# NG2092_LEFT_OV9282.net
KiCad netlist of a schematic drawn in Altium Designer
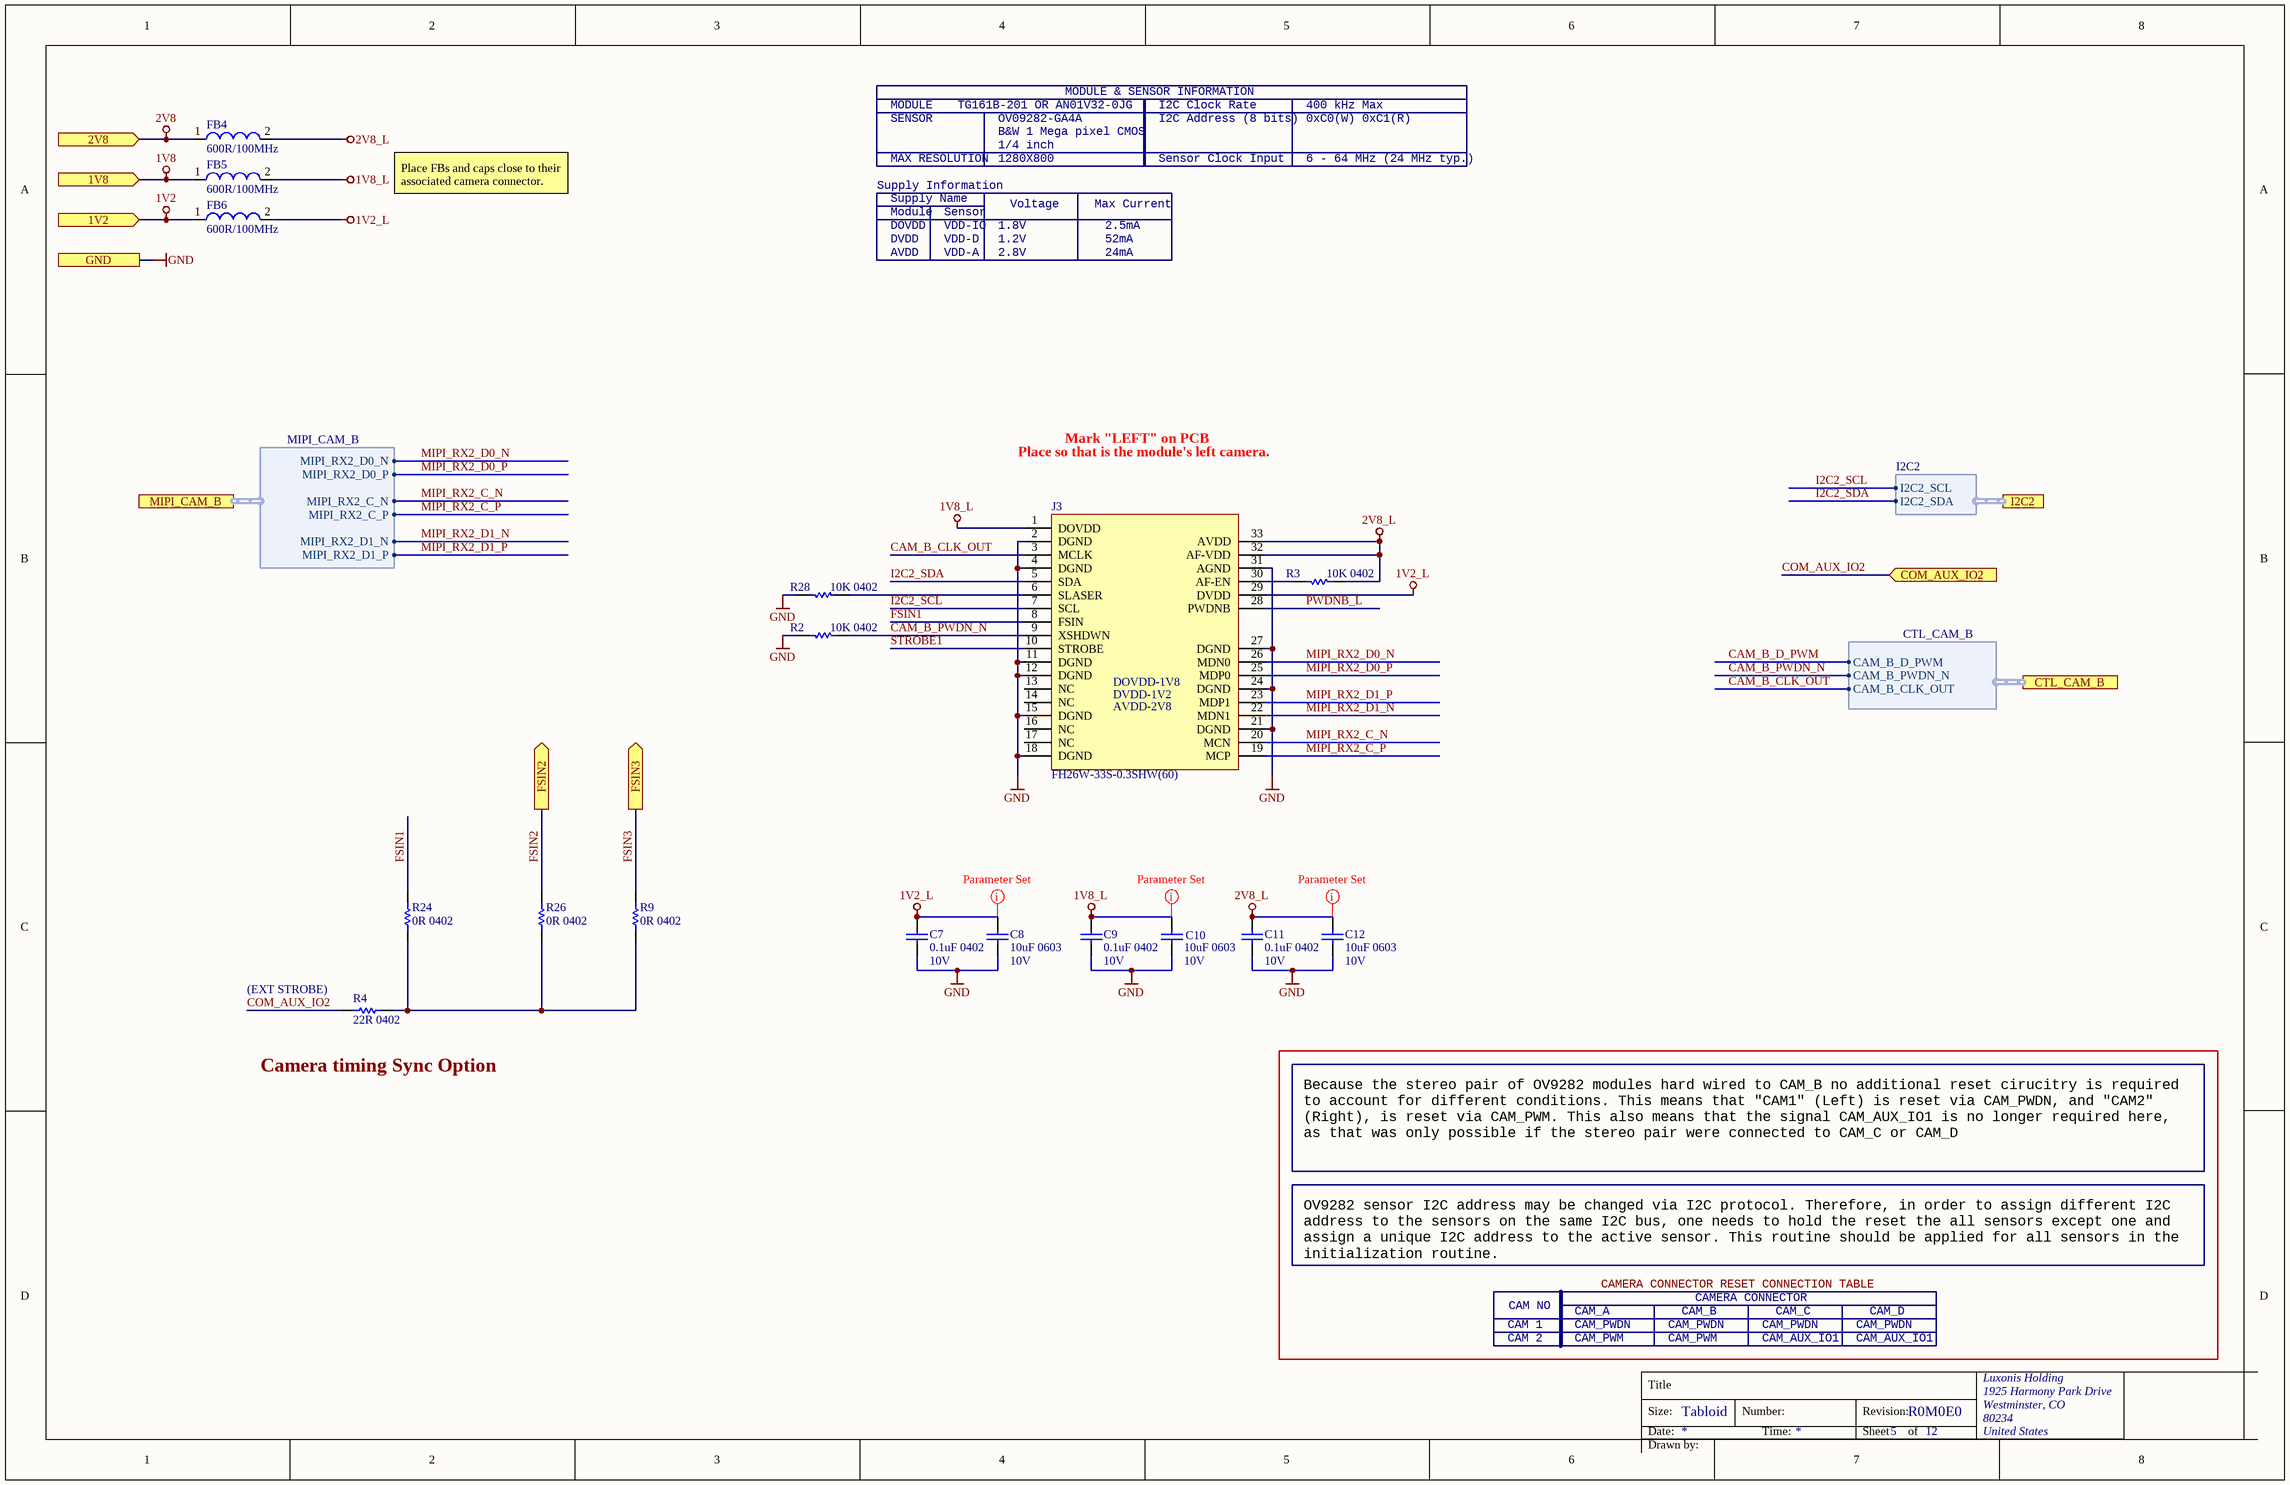
[diagram p0: NG2092_LEFT_OV9282.SchDoc]

(export (version "E")
  (design (tool "Eeschema 10.0.6"))
  (components
    (comp (ref "C7")
      (value "0.1uF 0402")
      (footprint "CAP_Altium_Vault_Generic:CAPC0402(1005)70_L")
      (description "CAP CER 0.1UF 10V X7R 0402 5%")
      (fields (field (name "TOLERANCE") "5%") (field (name "VOLTAGE RATING") "10V"))
      (libsource (lib "LuxonisMaster") (part "GRM155R71A104JA01D"))
    )
    (comp (ref "C8")
      (value "10uF 0603")
      (footprint "CAP_Altium_Vault_Generic:CAPC0603(1608)100_L")
      (description "CAP CER 10UF 10V X5R 0603 20%")
      (fields (field (name "TOLERANCE") "20%") (field (name "VOLTAGE RATING") "10V"))
      (libsource (lib "LuxonisMaster") (part "GRM188R61A106ME69D"))
    )
    (comp (ref "C9")
      (value "0.1uF 0402")
      (footprint "CAP_Altium_Vault_Generic:CAPC0402(1005)70_L")
      (description "CAP CER 0.1UF 10V X7R 0402 5%")
      (fields (field (name "TOLERANCE") "5%") (field (name "VOLTAGE RATING") "10V"))
      (libsource (lib "LuxonisMaster") (part "GRM155R71A104JA01D"))
    )
    (comp (ref "C10")
      (value "10uF 0603")
      (footprint "CAP_Altium_Vault_Generic:CAPC0603(1608)100_L")
      (description "CAP CER 10UF 10V X5R 0603 20%")
      (fields (field (name "TOLERANCE") "20%") (field (name "VOLTAGE RATING") "10V"))
      (libsource (lib "LuxonisMaster") (part "GRM188R61A106ME69D"))
    )
    (comp (ref "C11")
      (value "0.1uF 0402")
      (footprint "CAP_Altium_Vault_Generic:CAPC0402(1005)70_L")
      (description "CAP CER 0.1UF 10V X7R 0402 5%")
      (fields (field (name "TOLERANCE") "5%") (field (name "VOLTAGE RATING") "10V"))
      (libsource (lib "LuxonisMaster") (part "GRM155R71A104JA01D"))
    )
    (comp (ref "C12")
      (value "10uF 0603")
      (footprint "CAP_Altium_Vault_Generic:CAPC0603(1608)100_L")
      (description "CAP CER 10UF 10V X5R 0603 20%")
      (fields (field (name "TOLERANCE") "20%") (field (name "VOLTAGE RATING") "10V"))
      (libsource (lib "LuxonisMaster") (part "GRM188R61A106ME69D"))
    )
    (comp (ref "FB4")
      (value "600R/100MHz")
      (footprint "LuxonisMaster:2508056017Y2")
      (description "FERRITE BEAD, 0.1OHM, 2A, 0805, 600R/100MHz")
      (fields (field (name "TOLERANCE") "25%"))
      (libsource (lib "LuxonisMaster") (part "2508056017Y2"))
    )
    (comp (ref "FB5")
      (value "600R/100MHz")
      (footprint "LuxonisMaster:2508056017Y2")
      (description "FERRITE BEAD, 0.1OHM, 2A, 0805, 600R/100MHz")
      (fields (field (name "TOLERANCE") "25%"))
      (libsource (lib "LuxonisMaster") (part "2508056017Y2"))
    )
    (comp (ref "FB6")
      (value "600R/100MHz")
      (footprint "LuxonisMaster:2508056017Y2")
      (description "FERRITE BEAD, 0.1OHM, 2A, 0805, 600R/100MHz")
      (fields (field (name "TOLERANCE") "25%"))
      (libsource (lib "LuxonisMaster") (part "2508056017Y2"))
    )
    (comp (ref "J3")
      (value "FH26W-33S-0.3SHW(60)")
      (footprint "AC-PY003-OV9282")
      (description "FFC/FPC Connector, 33 Contact(s), 1 Row(s), Female, Right Angle, Surface Mount Terminal")
      (libsource (lib "NG2092") (part "AC_PY003-OV9282_CON"))
    )
    (comp (ref "R2")
      (value "10K 0402")
      (footprint "RES_Altium_Vault_Generic:RESC0402(1005)_L")
      (fields (field (name "TOLERANCE") "1%"))
      (libsource (lib "LuxonisMaster") (part "RC0402FR-1310KL"))
    )
    (comp (ref "R3")
      (value "10K 0402")
      (footprint "RES_Altium_Vault_Generic:RESC0402(1005)_L")
      (fields (field (name "TOLERANCE") "1%"))
      (libsource (lib "LuxonisMaster") (part "RC0402FR-1310KL"))
    )
    (comp (ref "R4")
      (value "22R 0402")
      (footprint "RES_Altium_Vault_Generic:RESC0402(1005)_L")
      (fields (field (name "TOLERANCE") "1%"))
      (libsource (lib "LuxonisMaster") (part "RC0402FR-1310KL"))
    )
    (comp (ref "R9")
      (value "0R 0402")
      (footprint "RES_Altium_Vault_Generic:RESC0402(1005)_L")
      (description "RES SMD 0 OHM JUMPER 1/16W 0402")
      (fields (field (name "TOLERANCE") "5%"))
      (libsource (lib "LuxonisMaster") (part "CRCW04020000Z0ED"))
    )
    (comp (ref "R24")
      (value "0R 0402")
      (footprint "RES_Altium_Vault_Generic:RESC0402(1005)_L")
      (description "RES SMD 0 OHM JUMPER 1/16W 0402")
      (fields (field (name "TOLERANCE") "5%"))
      (libsource (lib "LuxonisMaster") (part "CRCW04020000Z0ED"))
    )
    (comp (ref "R26")
      (value "0R 0402")
      (footprint "RES_Altium_Vault_Generic:RESC0402(1005)_L")
      (description "RES SMD 0 OHM JUMPER 1/16W 0402")
      (fields (field (name "TOLERANCE") "5%"))
      (libsource (lib "LuxonisMaster") (part "CRCW04020000Z0ED"))
    )
    (comp (ref "R28")
      (value "10K 0402")
      (footprint "RES_Altium_Vault_Generic:RESC0402(1005)_L")
      (fields (field (name "TOLERANCE") "1%"))
      (libsource (lib "LuxonisMaster") (part "RC0402FR-1310KL"))
    )
  )
  (nets
    (net (code "4") (name "/CAM_B_CLK_OUT") (class "Default")
      (node (ref "J3") (pin "3") (pinfunction "MCLK_3") (pintype "passive"))
    )
    (net (code "6") (name "/CAM_B_PWDN_N") (class "Default")
      (node (ref "J3") (pin "9") (pinfunction "XSHDWN_9") (pintype "passive"))
      (node (ref "R2") (pin "1") (pinfunction "1_1") (pintype "passive"))
    )
    (net (code "7") (name "/COM_AUX_IO2") (class "Default")
      (node (ref "R4") (pin "1") (pinfunction "1_1") (pintype "passive"))
    )
    (net (code "8") (name "/FSIN1") (class "Default")
      (node (ref "J3") (pin "8") (pinfunction "FSIN_8") (pintype "passive"))
      (node (ref "R24") (pin "2") (pinfunction "2_2") (pintype "passive"))
    )
    (net (code "9") (name "/FSIN2") (class "Default")
      (node (ref "R26") (pin "2") (pinfunction "2_2") (pintype "passive"))
    )
    (net (code "10") (name "/FSIN3") (class "Default")
      (node (ref "R9") (pin "1") (pinfunction "1_1") (pintype "passive"))
    )
    (net (code "11") (name "/I2C2_SCL") (class "Default")
      (node (ref "J3") (pin "7") (pinfunction "SCL_7") (pintype "passive"))
    )
    (net (code "12") (name "/I2C2_SDA") (class "Default")
      (node (ref "J3") (pin "5") (pinfunction "SDA_5") (pintype "passive"))
    )
    (net (code "13") (name "/MIPI_RX2_C_N") (class "Default")
      (node (ref "J3") (pin "20") (pinfunction "MCN_20") (pintype "passive"))
    )
    (net (code "14") (name "/MIPI_RX2_C_P") (class "Default")
      (node (ref "J3") (pin "19") (pinfunction "MCP_19") (pintype "passive"))
    )
    (net (code "15") (name "/MIPI_RX2_D0_N") (class "Default")
      (node (ref "J3") (pin "26") (pinfunction "MDN0_26") (pintype "passive"))
    )
    (net (code "16") (name "/MIPI_RX2_D0_P") (class "Default")
      (node (ref "J3") (pin "25") (pinfunction "MDP0_25") (pintype "passive"))
    )
    (net (code "17") (name "/MIPI_RX2_D1_N") (class "Default")
      (node (ref "J3") (pin "22") (pinfunction "MDN1_22") (pintype "passive"))
    )
    (net (code "18") (name "/MIPI_RX2_D1_P") (class "Default")
      (node (ref "J3") (pin "23") (pinfunction "MDP1_23") (pintype "passive"))
    )
    (net (code "19") (name "/PWDNB_L") (class "Default")
      (node (ref "J3") (pin "28") (pinfunction "PWDNB_28") (pintype "passive"))
    )
    (net (code "20") (name "/STROBE1") (class "Default")
      (node (ref "J3") (pin "10") (pinfunction "STROBE_10") (pintype "passive"))
    )
    (net (code "24") (name "1V2") (class "Default")
      (node (ref "FB6") (pin "1") (pinfunction "1_1") (pintype "passive"))
    )
    (net (code "25") (name "1V2_L") (class "Default")
      (node (ref "C7") (pin "2") (pinfunction "2_2") (pintype "passive"))
      (node (ref "C8") (pin "2") (pinfunction "2_2") (pintype "passive"))
      (node (ref "FB6") (pin "2") (pinfunction "2_2") (pintype "passive"))
      (node (ref "J3") (pin "29") (pinfunction "DVDD_29") (pintype "passive"))
    )
    (net (code "26") (name "1V8") (class "Default")
      (node (ref "FB5") (pin "1") (pinfunction "1_1") (pintype "passive"))
    )
    (net (code "27") (name "1V8_L") (class "Default")
      (node (ref "C10") (pin "2") (pinfunction "2_2") (pintype "passive"))
      (node (ref "C9") (pin "2") (pinfunction "2_2") (pintype "passive"))
      (node (ref "FB5") (pin "2") (pinfunction "2_2") (pintype "passive"))
      (node (ref "J3") (pin "1") (pinfunction "DOVDD_1") (pintype "passive"))
    )
    (net (code "28") (name "2V8") (class "Default")
      (node (ref "FB4") (pin "1") (pinfunction "1_1") (pintype "passive"))
    )
    (net (code "29") (name "2V8_L") (class "Default")
      (node (ref "C11") (pin "2") (pinfunction "2_2") (pintype "passive"))
      (node (ref "C12") (pin "2") (pinfunction "2_2") (pintype "passive"))
      (node (ref "FB4") (pin "2") (pinfunction "2_2") (pintype "passive"))
      (node (ref "J3") (pin "32") (pinfunction "AF-VDD_32") (pintype "passive"))
      (node (ref "J3") (pin "33") (pinfunction "AVDD_33") (pintype "passive"))
      (node (ref "R3") (pin "1") (pinfunction "1_1") (pintype "passive"))
    )
    (net (code "30") (name "GND") (class "Default")
      (node (ref "C10") (pin "1") (pinfunction "1_1") (pintype "passive"))
      (node (ref "C11") (pin "1") (pinfunction "1_1") (pintype "passive"))
      (node (ref "C12") (pin "1") (pinfunction "1_1") (pintype "passive"))
      (node (ref "C7") (pin "1") (pinfunction "1_1") (pintype "passive"))
      (node (ref "C8") (pin "1") (pinfunction "1_1") (pintype "passive"))
      (node (ref "C9") (pin "1") (pinfunction "1_1") (pintype "passive"))
      (node (ref "J3") (pin "11") (pinfunction "DGND_11") (pintype "passive"))
      (node (ref "J3") (pin "12") (pinfunction "DGND_12") (pintype "passive"))
      (node (ref "J3") (pin "15") (pinfunction "DGND_15") (pintype "passive"))
      (node (ref "J3") (pin "18") (pinfunction "DGND_18") (pintype "passive"))
      (node (ref "J3") (pin "2") (pinfunction "DGND_2") (pintype "passive"))
      (node (ref "J3") (pin "21") (pinfunction "DGND_21") (pintype "passive"))
      (node (ref "J3") (pin "24") (pinfunction "DGND_24") (pintype "passive"))
      (node (ref "J3") (pin "27") (pinfunction "DGND_27") (pintype "passive"))
      (node (ref "J3") (pin "31") (pinfunction "AGND_31") (pintype "passive"))
      (node (ref "J3") (pin "4") (pinfunction "DGND_4") (pintype "passive"))
      (node (ref "R2") (pin "2") (pinfunction "2_2") (pintype "passive"))
      (node (ref "R28") (pin "2") (pinfunction "2_2") (pintype "passive"))
    )
    (net (code "31") (name "Net-(J3-AF-EN)") (class "Default")
      (node (ref "J3") (pin "30") (pinfunction "AF-EN_30") (pintype "passive"))
      (node (ref "R3") (pin "2") (pinfunction "2_2") (pintype "passive"))
    )
    (net (code "32") (name "Net-(J3-SLASER)") (class "Default")
      (node (ref "J3") (pin "6") (pinfunction "SLASER_6") (pintype "passive"))
      (node (ref "R28") (pin "1") (pinfunction "1_1") (pintype "passive"))
    )
    (net (code "33") (name "Net-(R24-Pad1)") (class "Default")
      (node (ref "R24") (pin "1") (pinfunction "1_1") (pintype "passive"))
      (node (ref "R26") (pin "1") (pinfunction "1_1") (pintype "passive"))
      (node (ref "R4") (pin "2") (pinfunction "2_2") (pintype "passive"))
      (node (ref "R9") (pin "2") (pinfunction "2_2") (pintype "passive"))
    )
    (net (code "34") (name "unconnected-(J3-NC-Pad13)") (class "Default")
      (node (ref "J3") (pin "13") (pinfunction "NC_13") (pintype "passive"))
    )
    (net (code "35") (name "unconnected-(J3-NC-Pad14)") (class "Default")
      (node (ref "J3") (pin "14") (pinfunction "NC_14") (pintype "passive"))
    )
    (net (code "36") (name "unconnected-(J3-NC-Pad16)") (class "Default")
      (node (ref "J3") (pin "16") (pinfunction "NC_16") (pintype "passive"))
    )
    (net (code "37") (name "unconnected-(J3-NC-Pad17)") (class "Default")
      (node (ref "J3") (pin "17") (pinfunction "NC_17") (pintype "passive"))
    )
  )
)
